# testboard.net
KiCad netlist of a schematic drawn in EAGLE
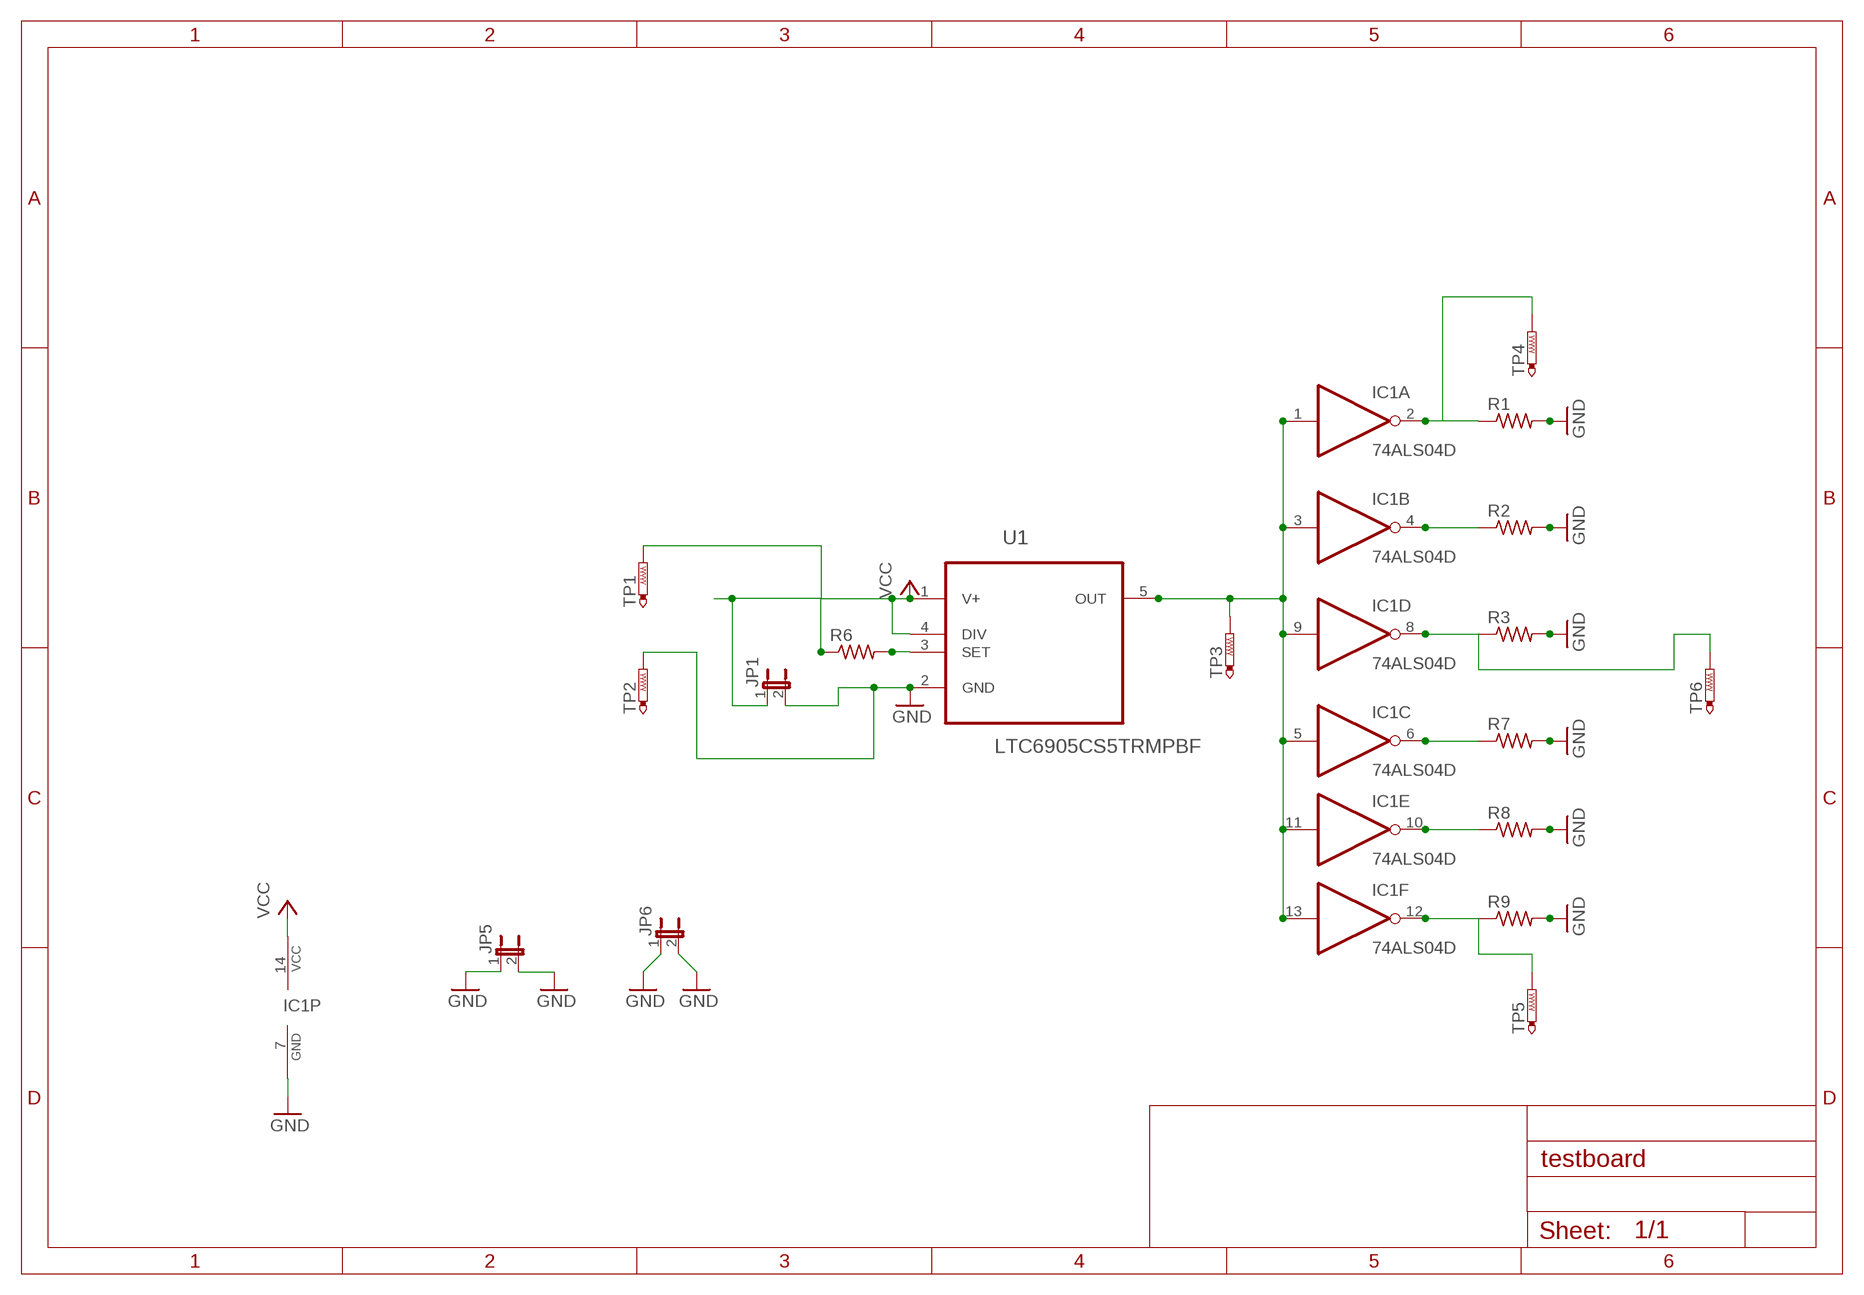
[diagram p0: schematic, sheet 1]

(export (version "E")
  (design (tool "Eeschema 10.0.6"))
  (components
    (comp (ref "IC1")
      (value "74ALS04D")
      (footprint "eagle-import:SO14")
      (libsource (lib "eagle-import") (part "7404DALS"))
    )
    (comp (ref "JP1")
      (value "JP1E")
      (footprint "eagle-import:JP1")
      (libsource (lib "eagle-import") (part "JP1E"))
    )
    (comp (ref "JP5")
      (value "JP1E")
      (footprint "eagle-import:JP1")
      (libsource (lib "eagle-import") (part "JP1E"))
    )
    (comp (ref "JP6")
      (value "JP1E")
      (footprint "eagle-import:JP1")
      (libsource (lib "eagle-import") (part "JP1E"))
    )
    (comp (ref "R1")
      (value "R-US_0204/2V")
      (footprint "eagle-import:0204V")
      (libsource (lib "eagle-import") (part "R-US_0204/2V"))
    )
    (comp (ref "R2")
      (value "R-US_0204/2V")
      (footprint "eagle-import:0204V")
      (libsource (lib "eagle-import") (part "R-US_0204/2V"))
    )
    (comp (ref "R3")
      (value "R-US_0204/2V")
      (footprint "eagle-import:0204V")
      (libsource (lib "eagle-import") (part "R-US_0204/2V"))
    )
    (comp (ref "R6")
      (value "R-US_0204/2V")
      (footprint "eagle-import:0204V")
      (libsource (lib "eagle-import") (part "R-US_0204/2V"))
    )
    (comp (ref "R7")
      (value "R-US_0204/2V")
      (footprint "eagle-import:0204V")
      (libsource (lib "eagle-import") (part "R-US_0204/2V"))
    )
    (comp (ref "R8")
      (value "R-US_0204/2V")
      (footprint "eagle-import:0204V")
      (libsource (lib "eagle-import") (part "R-US_0204/2V"))
    )
    (comp (ref "R9")
      (value "R-US_0204/2V")
      (footprint "eagle-import:0204V")
      (libsource (lib "eagle-import") (part "R-US_0204/2V"))
    )
    (comp (ref "TP1")
      (value "PTR1B2,54")
      (footprint "eagle-import:B2,54")
      (libsource (lib "eagle-import") (part "PTR1B2,54"))
    )
    (comp (ref "TP2")
      (value "PTR1B2,54")
      (footprint "eagle-import:B2,54")
      (libsource (lib "eagle-import") (part "PTR1B2,54"))
    )
    (comp (ref "TP3")
      (value "PTR1B2,54")
      (footprint "eagle-import:B2,54")
      (libsource (lib "eagle-import") (part "PTR1B2,54"))
    )
    (comp (ref "TP4")
      (value "PTR1B2,54")
      (footprint "eagle-import:B2,54")
      (libsource (lib "eagle-import") (part "PTR1B2,54"))
    )
    (comp (ref "TP5")
      (value "PTR1B2,54")
      (footprint "eagle-import:B2,54")
      (libsource (lib "eagle-import") (part "PTR1B2,54"))
    )
    (comp (ref "TP6")
      (value "PTR1B2,54")
      (footprint "eagle-import:B2,54")
      (libsource (lib "eagle-import") (part "PTR1B2,54"))
    )
    (comp (ref "U1")
      (value "LTC6905CS5TRMPBF")
      (footprint "eagle-import:SOT95P280X100-5N")
      (fields (field (name "MPN") "LTC6905CS5#TRMPBF"))
      (libsource (lib "eagle-import") (part "LTC6905CS5TRMPBF"))
    )
  )
  (nets
    (net (code "1") (name "GND") (class "Default")
      (node (ref "IC1") (pin "7") (pinfunction "GND_7") (pintype "power_in"))
      (node (ref "JP1") (pin "2") (pinfunction "2_2") (pintype "passive"))
      (node (ref "JP5") (pin "1") (pinfunction "1_1") (pintype "passive"))
      (node (ref "JP5") (pin "2") (pinfunction "2_2") (pintype "passive"))
      (node (ref "JP6") (pin "1") (pinfunction "1_1") (pintype "passive"))
      (node (ref "JP6") (pin "2") (pinfunction "2_2") (pintype "passive"))
      (node (ref "R1") (pin "2") (pinfunction "2_2") (pintype "passive"))
      (node (ref "R2") (pin "2") (pinfunction "2_2") (pintype "passive"))
      (node (ref "R3") (pin "2") (pinfunction "2_2") (pintype "passive"))
      (node (ref "R7") (pin "2") (pinfunction "2_2") (pintype "passive"))
      (node (ref "R8") (pin "2") (pinfunction "2_2") (pintype "passive"))
      (node (ref "R9") (pin "2") (pinfunction "2_2") (pintype "passive"))
      (node (ref "TP2") (pin "TP") (pinfunction "TP_TP") (pintype "input"))
      (node (ref "U1") (pin "2") (pinfunction "GND_2") (pintype "passive"))
    )
    (net (code "2") (name "Net-(IC1A-I)") (class "Default")
      (node (ref "IC1") (pin "1") (pinfunction "I_1") (pintype "input"))
      (node (ref "IC1") (pin "11") (pinfunction "I_11") (pintype "input"))
      (node (ref "IC1") (pin "13") (pinfunction "I_13") (pintype "input"))
      (node (ref "IC1") (pin "3") (pinfunction "I_3") (pintype "input"))
      (node (ref "IC1") (pin "5") (pinfunction "I_5") (pintype "input"))
      (node (ref "IC1") (pin "9") (pinfunction "I_9") (pintype "input"))
      (node (ref "TP3") (pin "TP") (pinfunction "TP_TP") (pintype "input"))
      (node (ref "U1") (pin "5") (pinfunction "OUT_5") (pintype "output"))
    )
    (net (code "3") (name "Net-(IC1A-O)") (class "Default")
      (node (ref "IC1") (pin "2") (pinfunction "O_2") (pintype "output"))
      (node (ref "R1") (pin "1") (pinfunction "1_1") (pintype "passive"))
      (node (ref "TP4") (pin "TP") (pinfunction "TP_TP") (pintype "input"))
    )
    (net (code "4") (name "Net-(IC1B-O)") (class "Default")
      (node (ref "IC1") (pin "4") (pinfunction "O_4") (pintype "output"))
      (node (ref "R2") (pin "1") (pinfunction "1_1") (pintype "passive"))
    )
    (net (code "5") (name "Net-(IC1C-O)") (class "Default")
      (node (ref "IC1") (pin "6") (pinfunction "O_6") (pintype "output"))
      (node (ref "R7") (pin "1") (pinfunction "1_1") (pintype "passive"))
    )
    (net (code "6") (name "Net-(IC1D-O)") (class "Default")
      (node (ref "IC1") (pin "8") (pinfunction "O_8") (pintype "output"))
      (node (ref "R3") (pin "1") (pinfunction "1_1") (pintype "passive"))
      (node (ref "TP6") (pin "TP") (pinfunction "TP_TP") (pintype "input"))
    )
    (net (code "7") (name "Net-(IC1E-O)") (class "Default")
      (node (ref "IC1") (pin "10") (pinfunction "O_10") (pintype "output"))
      (node (ref "R8") (pin "1") (pinfunction "1_1") (pintype "passive"))
    )
    (net (code "8") (name "Net-(IC1F-O)") (class "Default")
      (node (ref "IC1") (pin "12") (pinfunction "O_12") (pintype "output"))
      (node (ref "R9") (pin "1") (pinfunction "1_1") (pintype "passive"))
      (node (ref "TP5") (pin "TP") (pinfunction "TP_TP") (pintype "input"))
    )
    (net (code "9") (name "Net-(U1-SET)") (class "Default")
      (node (ref "R6") (pin "2") (pinfunction "2_2") (pintype "passive"))
      (node (ref "U1") (pin "3") (pinfunction "SET_3") (pintype "input"))
    )
    (net (code "10") (name "VCC") (class "Default")
      (node (ref "IC1") (pin "14") (pinfunction "VCC_14") (pintype "power_in"))
      (node (ref "JP1") (pin "1") (pinfunction "1_1") (pintype "passive"))
      (node (ref "R6") (pin "1") (pinfunction "1_1") (pintype "passive"))
      (node (ref "TP1") (pin "TP") (pinfunction "TP_TP") (pintype "input"))
      (node (ref "U1") (pin "1") (pinfunction "V+_1") (pintype "power_in"))
      (node (ref "U1") (pin "4") (pinfunction "DIV_4") (pintype "input"))
    )
  )
)
